# 555_astable_multivibrator.net
KiCad netlist of a schematic drawn in EAGLE
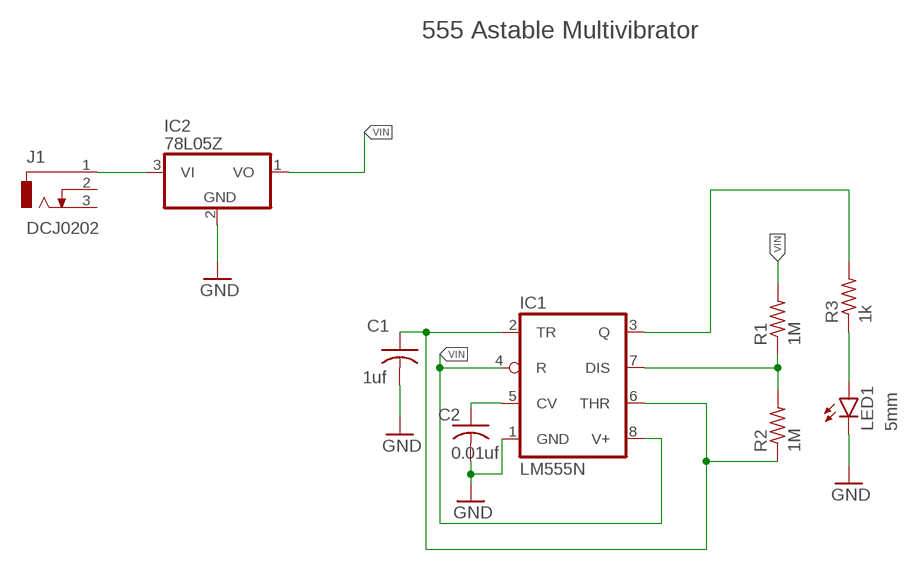
[diagram p0: schematic, sheet 1]

(export (version "E")
  (design (tool "Eeschema 10.0.6"))
  (components
    (comp (ref "C1")
      (value "1uf")
      (footprint "eagle-import:C050-024X044")
      (libsource (lib "eagle-import") (part "C-US050-024X044"))
    )
    (comp (ref "C2")
      (value "0.01uf")
      (footprint "eagle-import:C050-024X044")
      (libsource (lib "eagle-import") (part "C-US050-024X044"))
    )
    (comp (ref "IC1")
      (value "LM555N")
      (footprint "eagle-import:DIL08")
      (libsource (lib "eagle-import") (part "555NLM"))
    )
    (comp (ref "IC2")
      (value "78L05Z")
      (footprint "eagle-import:TO92")
      (libsource (lib "eagle-import") (part "78ZL05"))
    )
    (comp (ref "J1")
      (value "DCJ0202")
      (footprint "eagle-import:DCJ0202")
      (libsource (lib "eagle-import") (part "DCJ0202"))
    )
    (comp (ref "LED1")
      (value "5mm")
      (footprint "eagle-import:LED5MM")
      (libsource (lib "eagle-import") (part "LED5MM"))
    )
    (comp (ref "R1")
      (value "1M")
      (footprint "eagle-import:0207_2V")
      (libsource (lib "eagle-import") (part "R-US_0207/2V"))
    )
    (comp (ref "R2")
      (value "1M")
      (footprint "eagle-import:0207_2V")
      (libsource (lib "eagle-import") (part "R-US_0207/2V"))
    )
    (comp (ref "R3")
      (value "1k")
      (footprint "eagle-import:0207_2V")
      (libsource (lib "eagle-import") (part "R-US_0207/2V"))
    )
  )
  (nets
    (net (code "1") (name "GND") (class "Default")
      (node (ref "C1") (pin "2") (pinfunction "2_2") (pintype "passive"))
      (node (ref "C2") (pin "2") (pinfunction "2_2") (pintype "passive"))
      (node (ref "IC1") (pin "1") (pinfunction "GND_1") (pintype "power_in"))
      (node (ref "IC2") (pin "2") (pinfunction "GND_2") (pintype "passive"))
      (node (ref "LED1") (pin "K") (pinfunction "C_K") (pintype "passive"))
    )
    (net (code "2") (name "Net-(IC1-CV)") (class "Default")
      (node (ref "C2") (pin "1") (pinfunction "1_1") (pintype "passive"))
      (node (ref "IC1") (pin "5") (pinfunction "CV_5") (pintype "input"))
    )
    (net (code "3") (name "Net-(IC1-DIS)") (class "Default")
      (node (ref "IC1") (pin "7") (pinfunction "DIS_7") (pintype "input"))
      (node (ref "R1") (pin "1") (pinfunction "1_1") (pintype "passive"))
      (node (ref "R2") (pin "2") (pinfunction "2_2") (pintype "passive"))
    )
    (net (code "4") (name "Net-(IC1-Q)") (class "Default")
      (node (ref "IC1") (pin "3") (pinfunction "Q_3") (pintype "output"))
      (node (ref "R3") (pin "2") (pinfunction "2_2") (pintype "passive"))
    )
    (net (code "5") (name "Net-(IC1-THR)") (class "Default")
      (node (ref "C1") (pin "1") (pinfunction "1_1") (pintype "passive"))
      (node (ref "IC1") (pin "2") (pinfunction "TR_2") (pintype "input"))
      (node (ref "IC1") (pin "6") (pinfunction "THR_6") (pintype "input"))
      (node (ref "R2") (pin "1") (pinfunction "1_1") (pintype "passive"))
    )
    (net (code "6") (name "Net-(IC2-VI)") (class "Default")
      (node (ref "IC2") (pin "3") (pinfunction "VI_3") (pintype "input"))
      (node (ref "J1") (pin "1") (pinfunction "1_1") (pintype "passive"))
    )
    (net (code "7") (name "Net-(LED1-PadA)") (class "Default")
      (node (ref "LED1") (pin "A") (pinfunction "A_A") (pintype "passive"))
      (node (ref "R3") (pin "1") (pinfunction "1_1") (pintype "passive"))
    )
    (net (code "8") (name "VIN") (class "Default")
      (node (ref "IC1") (pin "4") (pinfunction "R_4") (pintype "input"))
      (node (ref "IC1") (pin "8") (pinfunction "V+_8") (pintype "power_in"))
      (node (ref "IC2") (pin "1") (pinfunction "VO_1") (pintype "passive"))
      (node (ref "R1") (pin "2") (pinfunction "2_2") (pintype "passive"))
    )
    (net (code "9") (name "unconnected-(J1-Pad2)") (class "Default")
      (node (ref "J1") (pin "2") (pinfunction "2_2") (pintype "passive"))
    )
    (net (code "10") (name "unconnected-(J1-Pad3)") (class "Default")
      (node (ref "J1") (pin "3") (pinfunction "3_3") (pintype "passive"))
    )
  )
)
